# OnOnfre_DevBoard_rev5.net
KiCad netlist of a schematic drawn in EAGLE
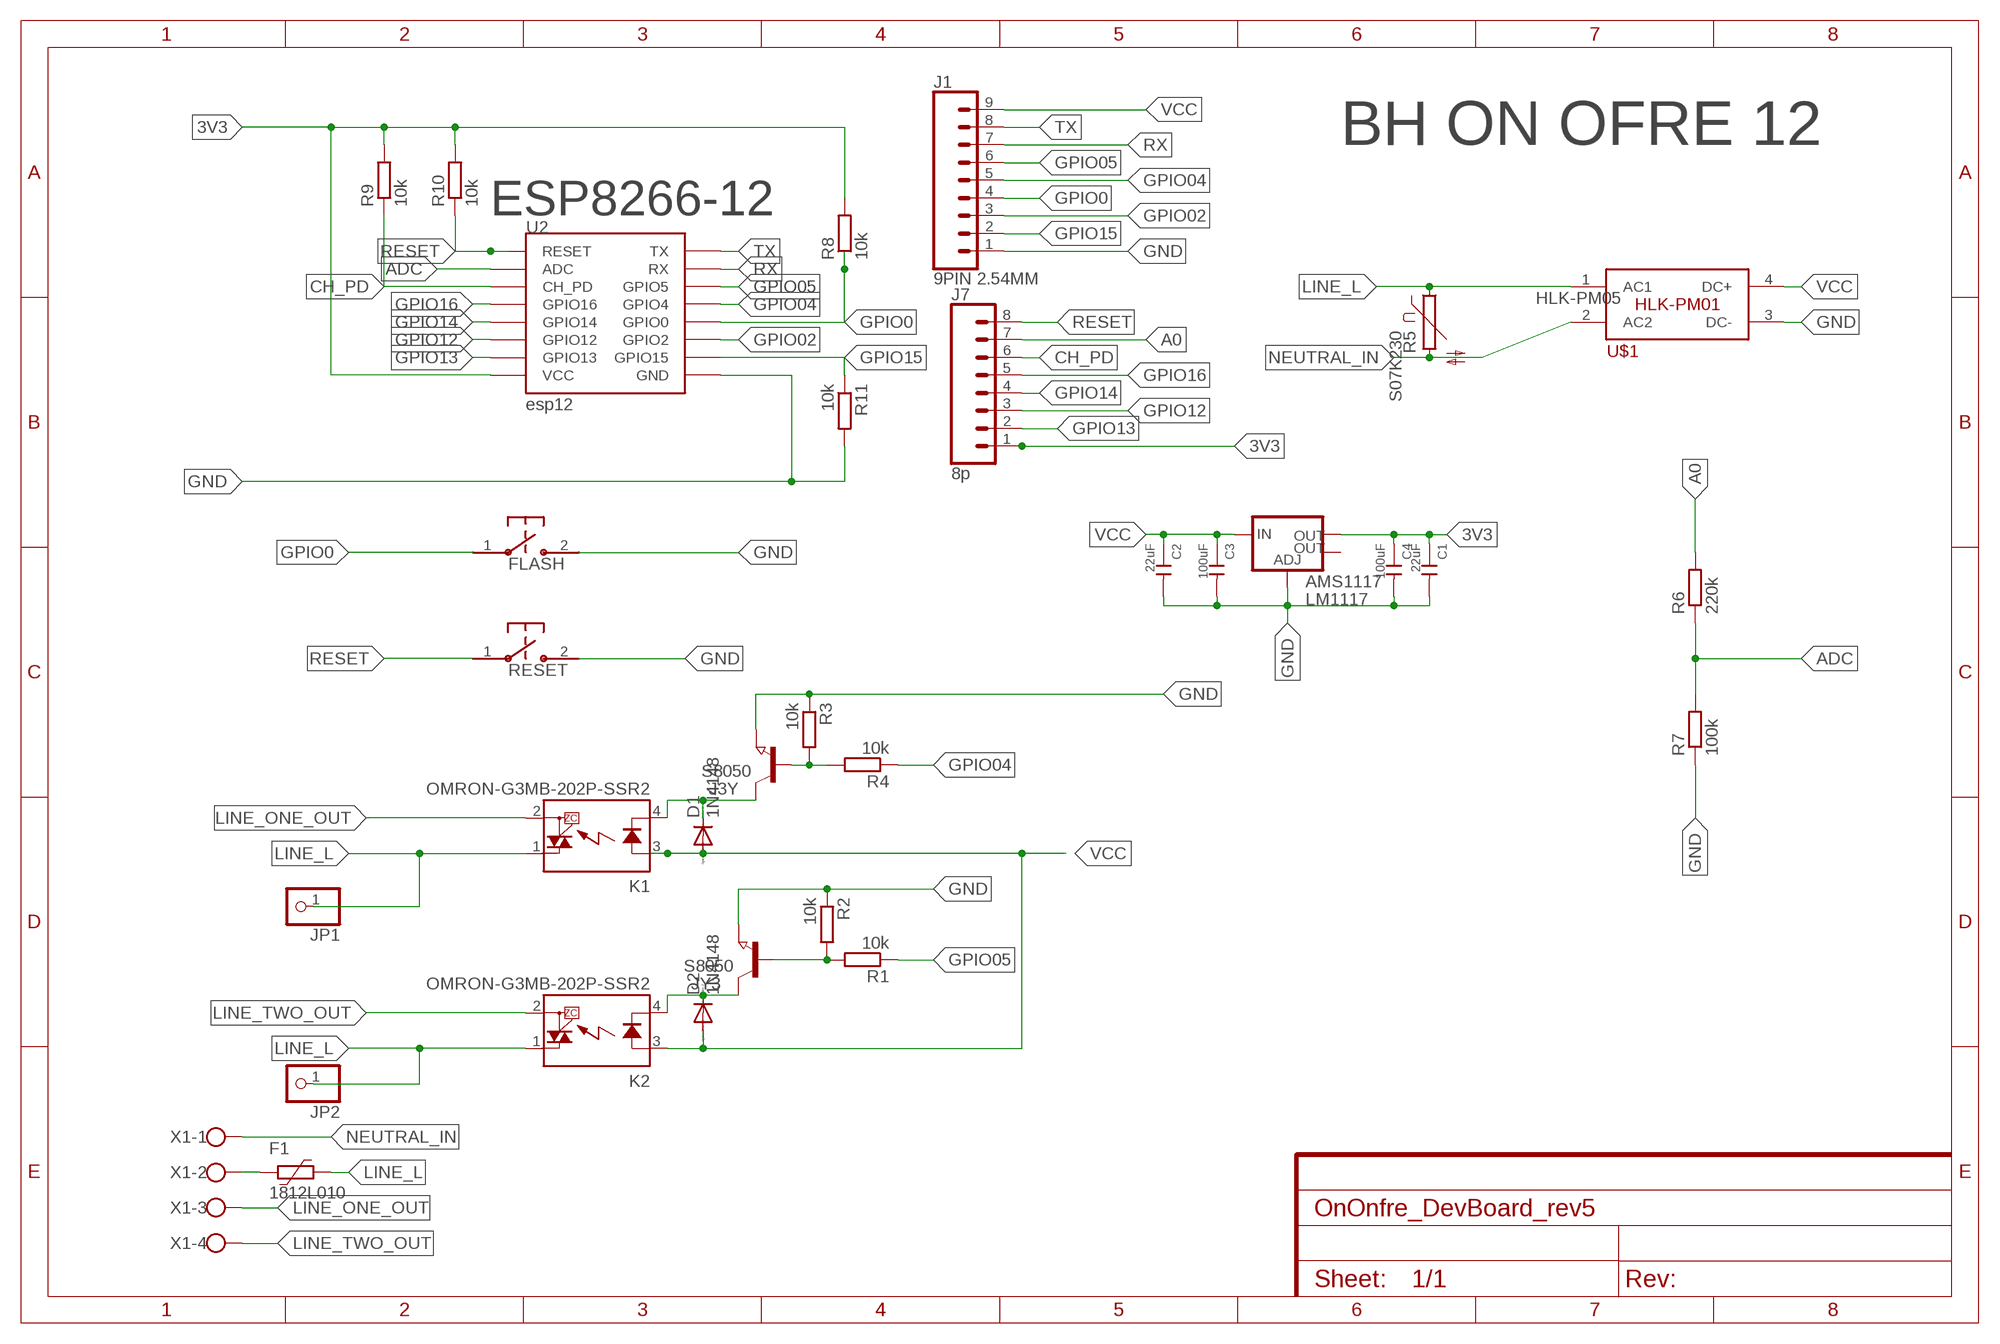
[diagram p0: schematic, sheet 1]

(export (version "E")
  (design (tool "Eeschema 10.0.6"))
  (components
    (comp (ref "AMS1117")
      (value "LM1117")
      (footprint "eagle-import:SOT223")
      (libsource (lib "eagle-import") (part "V_REG_LM1117SOT223"))
    )
    (comp (ref "C1")
      (value "22uF")
      (footprint "eagle-import:C1206")
      (fields (field (name "MPN") "CC1206KKX7RCBB102"))
      (libsource (lib "eagle-import") (part "CERAMIC-1NF-1KV-10%-X7R?(1206)"))
    )
    (comp (ref "C2")
      (value "22uF")
      (footprint "eagle-import:C1206")
      (fields (field (name "MPN") "CC1206KKX7RCBB102"))
      (libsource (lib "eagle-import") (part "CERAMIC-1NF-1KV-10%-X7R?(1206)"))
    )
    (comp (ref "C3")
      (value "100uF")
      (footprint "eagle-import:C1206")
      (fields (field (name "MPN") "CC1206KKX7RCBB102"))
      (libsource (lib "eagle-import") (part "CERAMIC-1NF-1KV-10%-X7R?(1206)"))
    )
    (comp (ref "C4")
      (value "100uF")
      (footprint "eagle-import:C1206")
      (fields (field (name "MPN") "CC1206KKX7RCBB102"))
      (libsource (lib "eagle-import") (part "CERAMIC-1NF-1KV-10%-X7R?(1206)"))
    )
    (comp (ref "D1")
      (value "1N4148")
      (footprint "eagle-import:SOD80C")
      (libsource (lib "eagle-import") (part "DIODE-SOD80C"))
    )
    (comp (ref "D2")
      (value "1N4148")
      (footprint "eagle-import:SOD80C")
      (libsource (lib "eagle-import") (part "DIODE-SOD80C"))
    )
    (comp (ref "F1")
      (value "1812L010")
      (footprint "eagle-import:1812L")
      (fields (field (name "MF") "Littelfuse"))
      (libsource (lib "eagle-import") (part "?1812L010"))
    )
    (comp (ref "FLASH")
      (value "B3U-1000P-2P-SMD")
      (footprint "eagle-import:B3U-1000P")
      (fields (field (name "MANUFACTURER") "Omron") (field (name "MPN") "B3U-1000P"))
      (libsource (lib "eagle-import") (part "B3U-1000P"))
    )
    (comp (ref "J1")
      (value "9PIN 2.54MM")
      (footprint "eagle-import:1X09")
      (libsource (lib "eagle-import") (part "CONN_09"))
    )
    (comp (ref "J3Y")
      (value "S8050")
      (footprint "eagle-import:SOT23")
      (libsource (lib "eagle-import") (part "NPN-TRANSISTOR_SOT23"))
    )
    (comp (ref "J7")
      (value "8p")
      (footprint "eagle-import:1X08")
      (libsource (lib "eagle-import") (part "CONN_08{dblquote}"))
    )
    (comp (ref "JP1")
      (value "PINHD-1X1")
      (footprint "eagle-import:1X01")
      (libsource (lib "eagle-import") (part "PINHD-1X1"))
    )
    (comp (ref "JP2")
      (value "PINHD-1X1")
      (footprint "eagle-import:1X01")
      (libsource (lib "eagle-import") (part "PINHD-1X1"))
    )
    (comp (ref "JY3")
      (value "S8050")
      (footprint "eagle-import:SOT23")
      (libsource (lib "eagle-import") (part "NPN-TRANSISTOR_SOT23"))
    )
    (comp (ref "K1")
      (value "OMRON-G3MB-202P-SSR2")
      (footprint "eagle-import:OMRON-G3MB-202P-SSR")
      (fields (field (name "MPN") "S202S02F"))
      (libsource (lib "eagle-import") (part "OMRON-G3MB-202P-SSR2"))
    )
    (comp (ref "K2")
      (value "OMRON-G3MB-202P-SSR2")
      (footprint "eagle-import:OMRON-G3MB-202P-SSR")
      (fields (field (name "MPN") "S202S02F"))
      (libsource (lib "eagle-import") (part "OMRON-G3MB-202P-SSR2"))
    )
    (comp (ref "R1")
      (value "10k")
      (footprint "eagle-import:R0603")
      (libsource (lib "eagle-import") (part "R-EU_R0603"))
    )
    (comp (ref "R2")
      (value "10k")
      (footprint "eagle-import:R0603")
      (libsource (lib "eagle-import") (part "R-EU_R0603"))
    )
    (comp (ref "R3")
      (value "10k")
      (footprint "eagle-import:R0603")
      (libsource (lib "eagle-import") (part "R-EU_R0603"))
    )
    (comp (ref "R4")
      (value "10k")
      (footprint "eagle-import:R0603")
      (libsource (lib "eagle-import") (part "R-EU_R0603"))
    )
    (comp (ref "R5")
      (value "S07K230")
      (footprint "eagle-import:S07K230")
      (libsource (lib "eagle-import") (part "S07K230"))
    )
    (comp (ref "R6")
      (value "220k")
      (footprint "eagle-import:R0603")
      (libsource (lib "eagle-import") (part "R-EU_R0603"))
    )
    (comp (ref "R7")
      (value "100k")
      (footprint "eagle-import:R0603")
      (libsource (lib "eagle-import") (part "R-EU_R0603"))
    )
    (comp (ref "R8")
      (value "10k")
      (footprint "eagle-import:R0603")
      (libsource (lib "eagle-import") (part "R-EU_R0603"))
    )
    (comp (ref "R9")
      (value "10k")
      (footprint "eagle-import:R0603")
      (libsource (lib "eagle-import") (part "R-EU_R0603"))
    )
    (comp (ref "R10")
      (value "10k")
      (footprint "eagle-import:R0603")
      (libsource (lib "eagle-import") (part "R-EU_R0603"))
    )
    (comp (ref "R11")
      (value "10k")
      (footprint "eagle-import:R0603")
      (libsource (lib "eagle-import") (part "R-EU_R0603"))
    )
    (comp (ref "RESET")
      (value "B3U-1000P-2P-SMD")
      (footprint "eagle-import:B3U-1000P")
      (fields (field (name "MANUFACTURER") "Omron") (field (name "MPN") "B3U-1000P"))
      (libsource (lib "eagle-import") (part "B3U-1000P"))
    )
    (comp (ref "U$1")
      (value "HLK-PM01")
      (footprint "eagle-import:HLK-PM01")
      (fields (field (name "MF") "Hi-link") (field (name "MP") "hlk-pm01"))
      (libsource (lib "eagle-import") (part "HLK-PM01"))
    )
    (comp (ref "U2")
      (value "esp12")
      (footprint "eagle-import:ESP12-SMD")
      (libsource (lib "eagle-import") (part "ESP12SMD"))
    )
    (comp (ref "X1")
      (value "W237-4")
      (footprint "eagle-import:W237-4")
      (libsource (lib "eagle-import") (part "W237-4"))
    )
  )
  (nets
    (net (code "1") (name "3V3") (class "Default")
      (node (ref "AMS1117") (pin "2") (pinfunction "OUT_2") (pintype "output"))
      (node (ref "C1") (pin "1") (pinfunction "1_1") (pintype "passive"))
      (node (ref "C4") (pin "1") (pinfunction "1_1") (pintype "passive"))
      (node (ref "J7") (pin "1") (pinfunction "1_1") (pintype "passive"))
      (node (ref "R10") (pin "2") (pinfunction "2_2") (pintype "passive"))
      (node (ref "R8") (pin "2") (pinfunction "2_2") (pintype "passive"))
      (node (ref "R9") (pin "2") (pinfunction "2_2") (pintype "passive"))
      (node (ref "U2") (pin "VCC") (pinfunction "VCC_VCC") (pintype "bidirectional"))
    )
    (net (code "2") (name "A0") (class "Default")
      (node (ref "J7") (pin "7") (pinfunction "7_7") (pintype "passive"))
      (node (ref "R6") (pin "2") (pinfunction "2_2") (pintype "passive"))
    )
    (net (code "3") (name "ADC") (class "Default")
      (node (ref "R6") (pin "1") (pinfunction "1_1") (pintype "passive"))
      (node (ref "R7") (pin "2") (pinfunction "2_2") (pintype "passive"))
      (node (ref "U2") (pin "ADC") (pinfunction "ADC_ADC") (pintype "bidirectional"))
    )
    (net (code "4") (name "CH_PD") (class "Default")
      (node (ref "J7") (pin "6") (pinfunction "6_6") (pintype "passive"))
      (node (ref "R9") (pin "1") (pinfunction "1_1") (pintype "passive"))
      (node (ref "U2") (pin "CH_PD") (pinfunction "CH_PD_CH_PD") (pintype "bidirectional"))
    )
    (net (code "5") (name "GND") (class "Default")
      (node (ref "AMS1117") (pin "1") (pinfunction "ADJ_1") (pintype "input"))
      (node (ref "C1") (pin "2") (pinfunction "2_2") (pintype "passive"))
      (node (ref "C2") (pin "2") (pinfunction "2_2") (pintype "passive"))
      (node (ref "C3") (pin "2") (pinfunction "2_2") (pintype "passive"))
      (node (ref "C4") (pin "2") (pinfunction "2_2") (pintype "passive"))
      (node (ref "FLASH") (pin "2") (pinfunction "P$2_2") (pintype "passive"))
      (node (ref "J1") (pin "1") (pinfunction "1_1") (pintype "passive"))
      (node (ref "J3Y") (pin "2") (pinfunction "E_2") (pintype "passive"))
      (node (ref "JY3") (pin "2") (pinfunction "E_2") (pintype "passive"))
      (node (ref "R11") (pin "2") (pinfunction "2_2") (pintype "passive"))
      (node (ref "R2") (pin "1") (pinfunction "1_1") (pintype "passive"))
      (node (ref "R3") (pin "1") (pinfunction "1_1") (pintype "passive"))
      (node (ref "R7") (pin "1") (pinfunction "1_1") (pintype "passive"))
      (node (ref "RESET") (pin "2") (pinfunction "P$2_2") (pintype "passive"))
      (node (ref "U$1") (pin "3") (pinfunction "DC-_3") (pintype "power_in"))
      (node (ref "U2") (pin "GND") (pinfunction "GND_GND") (pintype "bidirectional"))
    )
    (net (code "6") (name "GPIO0") (class "Default")
      (node (ref "FLASH") (pin "1") (pinfunction "P$1_1") (pintype "passive"))
      (node (ref "J1") (pin "4") (pinfunction "4_4") (pintype "passive"))
      (node (ref "R8") (pin "1") (pinfunction "1_1") (pintype "passive"))
      (node (ref "U2") (pin "GPIO0") (pinfunction "GPIO0_GPIO0") (pintype "bidirectional"))
    )
    (net (code "7") (name "GPIO02") (class "Default")
      (node (ref "J1") (pin "3") (pinfunction "3_3") (pintype "passive"))
      (node (ref "U2") (pin "GPIO2") (pinfunction "GPIO2_GPIO2") (pintype "bidirectional"))
    )
    (net (code "8") (name "GPIO04") (class "Default")
      (node (ref "J1") (pin "5") (pinfunction "5_5") (pintype "passive"))
      (node (ref "R4") (pin "1") (pinfunction "1_1") (pintype "passive"))
      (node (ref "U2") (pin "GPIO4") (pinfunction "GPIO4_GPIO4") (pintype "bidirectional"))
    )
    (net (code "9") (name "GPIO05") (class "Default")
      (node (ref "J1") (pin "6") (pinfunction "6_6") (pintype "passive"))
      (node (ref "R1") (pin "1") (pinfunction "1_1") (pintype "passive"))
      (node (ref "U2") (pin "GPIO5") (pinfunction "GPIO5_GPIO5") (pintype "bidirectional"))
    )
    (net (code "10") (name "GPIO12") (class "Default")
      (node (ref "J7") (pin "3") (pinfunction "3_3") (pintype "passive"))
      (node (ref "U2") (pin "GPIO12") (pinfunction "GPIO12_GPIO12") (pintype "bidirectional"))
    )
    (net (code "11") (name "GPIO13") (class "Default")
      (node (ref "J7") (pin "2") (pinfunction "2_2") (pintype "passive"))
      (node (ref "U2") (pin "GPIO13") (pinfunction "GPIO13_GPIO13") (pintype "bidirectional"))
    )
    (net (code "12") (name "GPIO14") (class "Default")
      (node (ref "J7") (pin "4") (pinfunction "4_4") (pintype "passive"))
      (node (ref "U2") (pin "GPIO14") (pinfunction "GPIO14_GPIO14") (pintype "bidirectional"))
    )
    (net (code "13") (name "GPIO15") (class "Default")
      (node (ref "J1") (pin "2") (pinfunction "2_2") (pintype "passive"))
      (node (ref "R11") (pin "1") (pinfunction "1_1") (pintype "passive"))
      (node (ref "U2") (pin "GPIO15") (pinfunction "GPIO15_GPIO15") (pintype "bidirectional"))
    )
    (net (code "14") (name "GPIO16") (class "Default")
      (node (ref "J7") (pin "5") (pinfunction "5_5") (pintype "passive"))
      (node (ref "U2") (pin "GPIO16") (pinfunction "GPIO16_GPIO16") (pintype "bidirectional"))
    )
    (net (code "15") (name "LINE_L") (class "Default")
      (node (ref "F1") (pin "1") (pinfunction "1_1") (pintype "passive"))
      (node (ref "JP1") (pin "1") (pinfunction "1_1") (pintype "passive"))
      (node (ref "JP2") (pin "1") (pinfunction "1_1") (pintype "passive"))
      (node (ref "K1") (pin "1") (pinfunction "DS1_1") (pintype "passive"))
      (node (ref "K2") (pin "1") (pinfunction "DS1_1") (pintype "passive"))
      (node (ref "R5") (pin "1") (pinfunction "1_1") (pintype "passive"))
      (node (ref "U$1") (pin "1") (pinfunction "AC1_1") (pintype "power_in"))
    )
    (net (code "16") (name "LINE_ONE_OUT") (class "Default")
      (node (ref "K1") (pin "2") (pinfunction "DS2_2") (pintype "passive"))
      (node (ref "X1") (pin "3") (pinfunction "KL_3") (pintype "passive"))
    )
    (net (code "17") (name "LINE_TWO_OUT") (class "Default")
      (node (ref "K2") (pin "2") (pinfunction "DS2_2") (pintype "passive"))
      (node (ref "X1") (pin "4") (pinfunction "KL_4") (pintype "passive"))
    )
    (net (code "18") (name "NEUTRAL_IN") (class "Default")
      (node (ref "R5") (pin "2") (pinfunction "2_2") (pintype "passive"))
      (node (ref "U$1") (pin "2") (pinfunction "AC2_2") (pintype "power_in"))
      (node (ref "X1") (pin "1") (pinfunction "KL_1") (pintype "passive"))
    )
    (net (code "19") (name "Net-(J3Y-B)") (class "Default")
      (node (ref "J3Y") (pin "1") (pinfunction "B_1") (pintype "passive"))
      (node (ref "R3") (pin "2") (pinfunction "2_2") (pintype "passive"))
      (node (ref "R4") (pin "2") (pinfunction "2_2") (pintype "passive"))
    )
    (net (code "20") (name "Net-(J3Y-C)") (class "Default")
      (node (ref "D1") (pin "C") (pinfunction "C_C") (pintype "passive"))
      (node (ref "J3Y") (pin "3") (pinfunction "C_3") (pintype "passive"))
      (node (ref "K1") (pin "4") (pinfunction "K_4") (pintype "passive"))
    )
    (net (code "21") (name "Net-(JY3-B)") (class "Default")
      (node (ref "JY3") (pin "1") (pinfunction "B_1") (pintype "passive"))
      (node (ref "R1") (pin "2") (pinfunction "2_2") (pintype "passive"))
      (node (ref "R2") (pin "2") (pinfunction "2_2") (pintype "passive"))
    )
    (net (code "22") (name "Net-(JY3-C)") (class "Default")
      (node (ref "D2") (pin "C") (pinfunction "C_C") (pintype "passive"))
      (node (ref "JY3") (pin "3") (pinfunction "C_3") (pintype "passive"))
      (node (ref "K2") (pin "4") (pinfunction "K_4") (pintype "passive"))
    )
    (net (code "23") (name "Net-(X1B-KL)") (class "Default")
      (node (ref "F1") (pin "2") (pinfunction "2_2") (pintype "passive"))
      (node (ref "X1") (pin "2") (pinfunction "KL_2") (pintype "passive"))
    )
    (net (code "24") (name "RESET") (class "Default")
      (node (ref "J7") (pin "8") (pinfunction "8_8") (pintype "passive"))
      (node (ref "R10") (pin "1") (pinfunction "1_1") (pintype "passive"))
      (node (ref "RESET") (pin "1") (pinfunction "P$1_1") (pintype "passive"))
      (node (ref "U2") (pin "RESET") (pinfunction "RESET_RESET") (pintype "bidirectional"))
    )
    (net (code "25") (name "RX") (class "Default")
      (node (ref "J1") (pin "7") (pinfunction "7_7") (pintype "passive"))
      (node (ref "U2") (pin "RXD0") (pinfunction "RX_RXD0") (pintype "bidirectional"))
    )
    (net (code "26") (name "TX") (class "Default")
      (node (ref "J1") (pin "8") (pinfunction "8_8") (pintype "passive"))
      (node (ref "U2") (pin "TXD0") (pinfunction "TX_TXD0") (pintype "bidirectional"))
    )
    (net (code "27") (name "VCC") (class "Default")
      (node (ref "AMS1117") (pin "3") (pinfunction "IN_3") (pintype "input"))
      (node (ref "C2") (pin "1") (pinfunction "1_1") (pintype "passive"))
      (node (ref "C3") (pin "1") (pinfunction "1_1") (pintype "passive"))
      (node (ref "D1") (pin "A") (pinfunction "A_A") (pintype "passive"))
      (node (ref "D2") (pin "A") (pinfunction "A_A") (pintype "passive"))
      (node (ref "J1") (pin "9") (pinfunction "9_9") (pintype "passive"))
      (node (ref "K1") (pin "3") (pinfunction "A_3") (pintype "passive"))
      (node (ref "K2") (pin "3") (pinfunction "A_3") (pintype "passive"))
      (node (ref "U$1") (pin "4") (pinfunction "DC+_4") (pintype "power_in"))
    )
    (net (code "28") (name "unconnected-(AMS1117-OUT-Pad4)") (class "Default")
      (node (ref "AMS1117") (pin "4") (pinfunction "OUT_4") (pintype "output"))
    )
  )
)
